# Shutdown_sch.net
KiCad netlist of a schematic drawn in Altium Designer
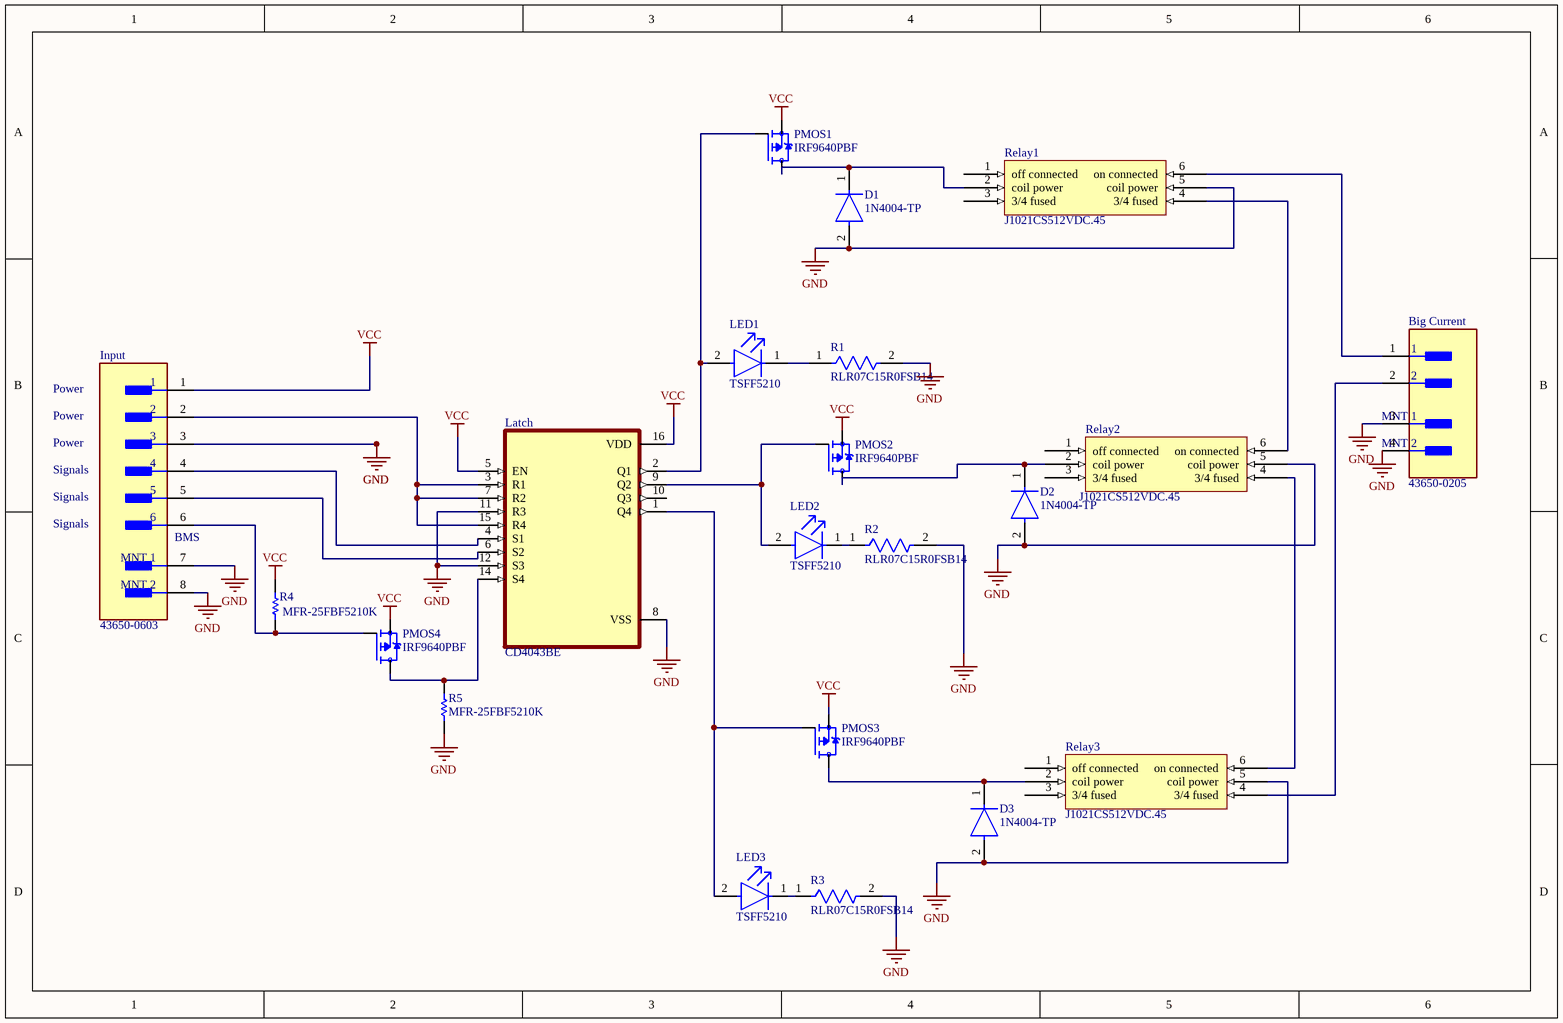
[diagram p0: Shutdown_sch.SchDoc]

(export (version "E")
  (design (tool "Eeschema 10.0.6"))
  (components
    (comp (ref "Big Current")
      (value "43650-0205")
      (footprint "FP-43650-0205-MFG")
      (description "43650-0205 Conn Wire to Board HDR 2 POS 3mm Solder RA Side Entry Thru-Hole Micro-Fit 3.0™ Tray")
      (libsource (lib "Altium Content Vault") (part "56ec3178a87b3978bdc1b3682cd516a"))
    )
    (comp (ref "D1")
      (value "1N4004-TP")
      (footprint "FP-DO-41-MFG")
      (description "DIODE GEN PURP 400V 1A DO41")
      (libsource (lib "Altium Content Vault") (part "d7152d700b627762746794eb795d46e"))
    )
    (comp (ref "D2")
      (value "1N4004-TP")
      (footprint "FP-DO-41-MFG")
      (description "DIODE GEN PURP 400V 1A DO41")
      (libsource (lib "Altium Content Vault") (part "d7152d700b627762746794eb795d46e"))
    )
    (comp (ref "D3")
      (value "1N4004-TP")
      (footprint "FP-DO-41-MFG")
      (description "DIODE GEN PURP 400V 1A DO41")
      (libsource (lib "Altium Content Vault") (part "d7152d700b627762746794eb795d46e"))
    )
    (comp (ref "Input")
      (value "43650-0603")
      (footprint "FP-43650-0603-MFG")
      (description "43650-0603 Conn Power HDR 6 POS 3mm Solder RA Thru-Hole 6 Terminal 1 Port Micro-Fit 3.0™ Frame")
      (libsource (lib "Altium Content Vault") (part "888702565824d4351783d317a98461b"))
    )
    (comp (ref "Latch")
      (value "CD4043BE")
      (footprint "DIP794W45P254L1969H508Q16")
      (description "CMOS Quad NOR R/S Latch with 3-State Outputs 16-PDIP -55 to 125")
      (fields
        (field (name "MF") "Texas Instruments")
        (field (name "BUYPART") "https://www.snapeda.com/parts/CD4043BE/Texas%20Instruments/view-part/577167/?ref=eda")
      )
      (libsource (lib "CD4043BE") (part "CD4043BE"))
    )
    (comp (ref "LED1")
      (value "TSFF5210")
      (footprint "FP-6_544-5258_09-4-MFG")
      (description "TSFF5210 TSFF5210 IR LED, 870nm, T-1 3/4 (5mm) Through Hole package")
      (libsource (lib "Altium Content Vault") (part "8706943c75ba83719d021d2fdc84c58"))
    )
    (comp (ref "LED2")
      (value "TSFF5210")
      (footprint "FP-6_544-5258_09-4-MFG")
      (description "TSFF5210 TSFF5210 IR LED, 870nm, T-1 3/4 (5mm) Through Hole package")
      (libsource (lib "Altium Content Vault") (part "8706943c75ba83719d021d2fdc84c58"))
    )
    (comp (ref "LED3")
      (value "TSFF5210")
      (footprint "FP-6_544-5258_09-4-MFG")
      (description "TSFF5210 TSFF5210 IR LED, 870nm, T-1 3/4 (5mm) Through Hole package")
      (libsource (lib "Altium Content Vault") (part "8706943c75ba83719d021d2fdc84c58"))
    )
    (comp (ref "PMOS1")
      (value "IRF9640PBF")
      (footprint "TO254P1052X465X1989-3")
      (description "P-Channel 200V 11A (Tc) 125W (Tc) Through Hole TO-220AB")
      (fields (field (name "MF") "Vishay Siliconix"))
      (libsource (lib "IRF9640PBF") (part "IRF9640PBF"))
    )
    (comp (ref "PMOS2")
      (value "IRF9640PBF")
      (footprint "TO254P1052X465X1989-3")
      (description "P-Channel 200V 11A (Tc) 125W (Tc) Through Hole TO-220AB")
      (fields (field (name "MF") "Vishay Siliconix"))
      (libsource (lib "IRF9640PBF") (part "IRF9640PBF"))
    )
    (comp (ref "PMOS3")
      (value "IRF9640PBF")
      (footprint "TO254P1052X465X1989-3")
      (description "P-Channel 200V 11A (Tc) 125W (Tc) Through Hole TO-220AB")
      (fields (field (name "MF") "Vishay Siliconix"))
      (libsource (lib "IRF9640PBF") (part "IRF9640PBF"))
    )
    (comp (ref "PMOS4")
      (value "IRF9640PBF")
      (footprint "TO254P1052X465X1989-3")
      (description "P-Channel 200V 11A (Tc) 125W (Tc) Through Hole TO-220AB")
      (fields (field (name "MF") "Vishay Siliconix"))
      (libsource (lib "IRF9640PBF") (part "IRF9640PBF"))
    )
    (comp (ref "R1")
      (value "RLR07C15R0FSB14")
      (footprint "FP-RLR07-MFG")
      (description "RLR07C15R0FSB14 Res Metal Film 15 Ohm 1% 1/4W ±100ppm/°C 0.001% Conformal AXL Thru-Hole Bulk")
      (fields (field (name "TOLERANCE") "1%"))
      (libsource (lib "Altium Content Vault") (part "1029c3af85768c4190bb7ad29bc67b5"))
    )
    (comp (ref "R2")
      (value "RLR07C15R0FSB14")
      (footprint "FP-RLR07-MFG")
      (description "RLR07C15R0FSB14 Res Metal Film 15 Ohm 1% 1/4W ±100ppm/°C 0.001% Conformal AXL Thru-Hole Bulk")
      (fields (field (name "TOLERANCE") "1%"))
      (libsource (lib "Altium Content Vault") (part "1029c3af85768c4190bb7ad29bc67b5"))
    )
    (comp (ref "R3")
      (value "RLR07C15R0FSB14")
      (footprint "FP-RLR07-MFG")
      (description "RLR07C15R0FSB14 Res Metal Film 15 Ohm 1% 1/4W ±100ppm/°C 0.001% Conformal AXL Thru-Hole Bulk")
      (fields (field (name "TOLERANCE") "1%"))
      (libsource (lib "Altium Content Vault") (part "1029c3af85768c4190bb7ad29bc67b5"))
    )
    (comp (ref "R4")
      (value "MFR-25FBF5210K")
      (footprint "RESA60-630X240")
      (description "Axial Resistor, 10 KOhm, +/- 1%, 0.25 W, -55 to 155 degC, 2-Pin THD, RoHS, Bulk")
      (fields (field (name "TOLERANCE") "1%") (field (name "MANUFACTURER") "Yageo"))
      (libsource (lib "Altium Content Vault") (part "RES-2"))
    )
    (comp (ref "R5")
      (value "MFR-25FBF5210K")
      (footprint "RESA60-630X240")
      (description "Axial Resistor, 10 KOhm, +/- 1%, 0.25 W, -55 to 155 degC, 2-Pin THD, RoHS, Bulk")
      (fields (field (name "TOLERANCE") "1%") (field (name "MANUFACTURER") "Yageo"))
      (libsource (lib "Altium Content Vault") (part "RES-2"))
    )
    (comp (ref "Relay1")
      (value "J1021CS512VDC.45")
      (footprint "J1021CS512VDC.45-Footprint-2")
      (libsource (lib "Luke Johnson") (part "J1021CS512VDC.45-Symbol-1"))
    )
    (comp (ref "Relay2")
      (value "J1021CS512VDC.45")
      (footprint "J1021CS512VDC.45-Footprint-2")
      (libsource (lib "Luke Johnson") (part "J1021CS512VDC.45-Symbol-1"))
    )
    (comp (ref "Relay3")
      (value "J1021CS512VDC.45")
      (footprint "J1021CS512VDC.45-Footprint-2")
      (libsource (lib "Luke Johnson") (part "J1021CS512VDC.45-Symbol-1"))
    )
  )
  (nets
    (net (code "1") (name "GND") (class "Default")
      (node (ref "Big Current") (pin "3") (pinfunction "MNT_1_3") (pintype "passive"))
      (node (ref "Big Current") (pin "4") (pinfunction "MNT_2_4") (pintype "passive"))
      (node (ref "D1") (pin "2") (pinfunction "A_2") (pintype "passive"))
      (node (ref "D2") (pin "2") (pinfunction "A_2") (pintype "passive"))
      (node (ref "D3") (pin "2") (pinfunction "A_2") (pintype "passive"))
      (node (ref "Input") (pin "3") (pinfunction "3_3") (pintype "passive"))
      (node (ref "Input") (pin "7") (pinfunction "MNT_1_7") (pintype "passive"))
      (node (ref "Input") (pin "8") (pinfunction "MNT_2_8") (pintype "passive"))
      (node (ref "Latch") (pin "11") (pinfunction "R3_11") (pintype "input"))
      (node (ref "Latch") (pin "12") (pinfunction "S3_12") (pintype "input"))
      (node (ref "Latch") (pin "8") (pinfunction "VSS_8") (pintype "power_in"))
      (node (ref "R1") (pin "2") (pinfunction "2_2") (pintype "passive"))
      (node (ref "R2") (pin "2") (pinfunction "2_2") (pintype "passive"))
      (node (ref "R3") (pin "2") (pinfunction "2_2") (pintype "passive"))
      (node (ref "R5") (pin "1") (pinfunction "1_1") (pintype "passive"))
      (node (ref "Relay1") (pin "5") (pinfunction "coil_power_5") (pintype "input"))
      (node (ref "Relay2") (pin "5") (pinfunction "coil_power_5") (pintype "input"))
      (node (ref "Relay3") (pin "5") (pinfunction "coil_power_5") (pintype "input"))
    )
    (net (code "2") (name "Net-(Big Current-Pad2)") (class "Default")
      (node (ref "Big Current") (pin "2") (pinfunction "2_2") (pintype "passive"))
      (node (ref "Relay3") (pin "4") (pinfunction "3/4_fused_4") (pintype "input"))
    )
    (net (code "3") (name "Net-(D1-C)") (class "Default")
      (node (ref "D1") (pin "1") (pinfunction "C_1") (pintype "passive"))
      (node (ref "PMOS1") (pin "2") (pinfunction "D_2") (pintype "passive"))
      (node (ref "Relay1") (pin "2") (pinfunction "coil_power_2") (pintype "input"))
    )
    (net (code "4") (name "Net-(D2-C)") (class "Default")
      (node (ref "D2") (pin "1") (pinfunction "C_1") (pintype "passive"))
      (node (ref "PMOS2") (pin "2") (pinfunction "D_2") (pintype "passive"))
      (node (ref "Relay2") (pin "2") (pinfunction "coil_power_2") (pintype "input"))
    )
    (net (code "5") (name "Net-(D3-C)") (class "Default")
      (node (ref "D3") (pin "1") (pinfunction "C_1") (pintype "passive"))
      (node (ref "PMOS3") (pin "2") (pinfunction "D_2") (pintype "passive"))
      (node (ref "Relay3") (pin "2") (pinfunction "coil_power_2") (pintype "input"))
    )
    (net (code "6") (name "Net-(LED1-A)") (class "Default")
      (node (ref "LED1") (pin "2") (pinfunction "A_2") (pintype "passive"))
      (node (ref "Latch") (pin "2") (pinfunction "Q1_2") (pintype "output"))
      (node (ref "PMOS1") (pin "1") (pinfunction "G_1") (pintype "passive"))
    )
    (net (code "7") (name "Net-(LED1-C)") (class "Default")
      (node (ref "LED1") (pin "1") (pinfunction "C_1") (pintype "passive"))
      (node (ref "R1") (pin "1") (pinfunction "1_1") (pintype "passive"))
    )
    (net (code "8") (name "Net-(LED2-A)") (class "Default")
      (node (ref "LED2") (pin "2") (pinfunction "A_2") (pintype "passive"))
      (node (ref "Latch") (pin "9") (pinfunction "Q2_9") (pintype "output"))
      (node (ref "PMOS2") (pin "1") (pinfunction "G_1") (pintype "passive"))
    )
    (net (code "9") (name "Net-(LED2-C)") (class "Default")
      (node (ref "LED2") (pin "1") (pinfunction "C_1") (pintype "passive"))
      (node (ref "R2") (pin "1") (pinfunction "1_1") (pintype "passive"))
    )
    (net (code "10") (name "Net-(LED3-A)") (class "Default")
      (node (ref "LED3") (pin "2") (pinfunction "A_2") (pintype "passive"))
      (node (ref "Latch") (pin "1") (pinfunction "Q4_1") (pintype "output"))
      (node (ref "PMOS3") (pin "1") (pinfunction "G_1") (pintype "passive"))
    )
    (net (code "11") (name "Net-(LED3-C)") (class "Default")
      (node (ref "LED3") (pin "1") (pinfunction "C_1") (pintype "passive"))
      (node (ref "R3") (pin "1") (pinfunction "1_1") (pintype "passive"))
    )
    (net (code "12") (name "Net-(Latch-R1)") (class "Default")
      (node (ref "Input") (pin "2") (pinfunction "2_2") (pintype "passive"))
      (node (ref "Latch") (pin "15") (pinfunction "R4_15") (pintype "input"))
      (node (ref "Latch") (pin "3") (pinfunction "R1_3") (pintype "input"))
      (node (ref "Latch") (pin "7") (pinfunction "R2_7") (pintype "input"))
    )
    (net (code "13") (name "Net-(Latch-S1)") (class "Default")
      (node (ref "Input") (pin "4") (pinfunction "4_4") (pintype "passive"))
      (node (ref "Latch") (pin "4") (pinfunction "S1_4") (pintype "input"))
    )
    (net (code "14") (name "Net-(Latch-S2)") (class "Default")
      (node (ref "Input") (pin "5") (pinfunction "5_5") (pintype "passive"))
      (node (ref "Latch") (pin "6") (pinfunction "S2_6") (pintype "input"))
    )
    (net (code "15") (name "Net-(Latch-S4)") (class "Default")
      (node (ref "Latch") (pin "14") (pinfunction "S4_14") (pintype "input"))
      (node (ref "PMOS4") (pin "2") (pinfunction "D_2") (pintype "passive"))
      (node (ref "R5") (pin "2") (pinfunction "2_2") (pintype "passive"))
    )
    (net (code "16") (name "Net-(PMOS4-G)") (class "Default")
      (node (ref "Input") (pin "6") (pinfunction "6_6") (pintype "passive"))
      (node (ref "PMOS4") (pin "1") (pinfunction "G_1") (pintype "passive"))
      (node (ref "R4") (pin "1") (pinfunction "1_1") (pintype "passive"))
    )
    (net (code "17") (name "Net-(Relay1-on_connected)") (class "Default")
      (node (ref "Big Current") (pin "1") (pinfunction "1_1") (pintype "passive"))
      (node (ref "Relay1") (pin "6") (pinfunction "on_connected_6") (pintype "input"))
    )
    (net (code "18") (name "Net-(Relay2-on_connected)") (class "Default")
      (node (ref "Relay1") (pin "4") (pinfunction "3/4_fused_4") (pintype "input"))
      (node (ref "Relay2") (pin "6") (pinfunction "on_connected_6") (pintype "input"))
    )
    (net (code "19") (name "Net-(Relay3-on_connected)") (class "Default")
      (node (ref "Relay2") (pin "4") (pinfunction "3/4_fused_4") (pintype "input"))
      (node (ref "Relay3") (pin "6") (pinfunction "on_connected_6") (pintype "input"))
    )
    (net (code "20") (name "VCC") (class "Default")
      (node (ref "Input") (pin "1") (pinfunction "1_1") (pintype "passive"))
      (node (ref "Latch") (pin "16") (pinfunction "VDD_16") (pintype "power_in"))
      (node (ref "Latch") (pin "5") (pinfunction "EN_5") (pintype "input"))
      (node (ref "PMOS1") (pin "3") (pinfunction "S_3") (pintype "passive"))
      (node (ref "PMOS2") (pin "3") (pinfunction "S_3") (pintype "passive"))
      (node (ref "PMOS3") (pin "3") (pinfunction "S_3") (pintype "passive"))
      (node (ref "PMOS4") (pin "3") (pinfunction "S_3") (pintype "passive"))
      (node (ref "R4") (pin "2") (pinfunction "2_2") (pintype "passive"))
    )
    (net (code "21") (name "unconnected-(Latch-Q3-Pad10)") (class "Default")
      (node (ref "Latch") (pin "10") (pinfunction "Q3_10") (pintype "output"))
    )
    (net (code "22") (name "unconnected-(Relay1-3{slash}4_fused-Pad3)") (class "Default")
      (node (ref "Relay1") (pin "3") (pinfunction "3/4_fused_3") (pintype "input"))
    )
    (net (code "23") (name "unconnected-(Relay1-off_connected-Pad1)") (class "Default")
      (node (ref "Relay1") (pin "1") (pinfunction "off_connected_1") (pintype "input"))
    )
    (net (code "24") (name "unconnected-(Relay2-3{slash}4_fused-Pad3)") (class "Default")
      (node (ref "Relay2") (pin "3") (pinfunction "3/4_fused_3") (pintype "input"))
    )
    (net (code "25") (name "unconnected-(Relay2-off_connected-Pad1)") (class "Default")
      (node (ref "Relay2") (pin "1") (pinfunction "off_connected_1") (pintype "input"))
    )
    (net (code "26") (name "unconnected-(Relay3-3{slash}4_fused-Pad3)") (class "Default")
      (node (ref "Relay3") (pin "3") (pinfunction "3/4_fused_3") (pintype "input"))
    )
    (net (code "27") (name "unconnected-(Relay3-off_connected-Pad1)") (class "Default")
      (node (ref "Relay3") (pin "1") (pinfunction "off_connected_1") (pintype "input"))
    )
  )
)
